# Expansition.net
KiCad netlist of a schematic drawn in Altium Designer
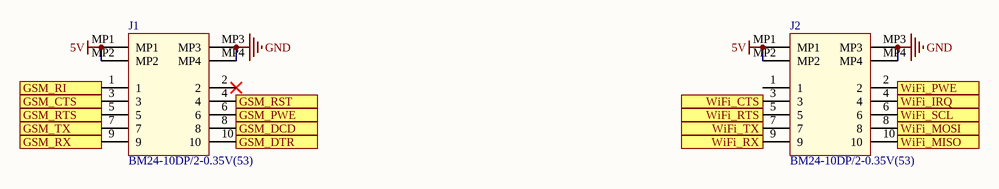
[diagram p0: Expansition.SchDoc]

(export (version "E")
  (design (tool "Eeschema 10.0.6"))
  (components
    (comp (ref "J1")
      (value "BM24-10DP/2-0.35V(53)")
      (footprint "HIROSE BM2410DP")
      (description "Board to Board Connector")
      (fields (field (name "MANUFACTURER") "Hirose"))
      (libsource (lib "yildizIoT Library") (part "12 Pin (10 + 2 Power) B2B Header"))
    )
    (comp (ref "J2")
      (value "BM24-10DP/2-0.35V(53)")
      (footprint "HIROSE BM2410DP")
      (description "Board to Board Connector")
      (fields (field (name "MANUFACTURER") "Hirose"))
      (libsource (lib "yildizIoT Library") (part "12 Pin (10 + 2 Power) B2B Header"))
    )
  )
  (nets
    (net (code "1") (name "/GSM_CTS") (class "Default")
      (node (ref "J1") (pin "3") (pinfunction "3_3") (pintype "passive"))
    )
    (net (code "2") (name "/GSM_DCD") (class "Default")
      (node (ref "J1") (pin "8") (pinfunction "8_8") (pintype "passive"))
    )
    (net (code "3") (name "/GSM_DTR") (class "Default")
      (node (ref "J1") (pin "10") (pinfunction "10_10") (pintype "passive"))
    )
    (net (code "4") (name "/GSM_PWE") (class "Default")
      (node (ref "J1") (pin "6") (pinfunction "6_6") (pintype "passive"))
    )
    (net (code "5") (name "/GSM_RI") (class "Default")
      (node (ref "J1") (pin "1") (pinfunction "1_1") (pintype "passive"))
    )
    (net (code "6") (name "/GSM_RST") (class "Default")
      (node (ref "J1") (pin "4") (pinfunction "4_4") (pintype "passive"))
    )
    (net (code "7") (name "/GSM_RTS") (class "Default")
      (node (ref "J1") (pin "5") (pinfunction "5_5") (pintype "passive"))
    )
    (net (code "8") (name "/GSM_RX") (class "Default")
      (node (ref "J1") (pin "9") (pinfunction "9_9") (pintype "passive"))
    )
    (net (code "9") (name "/GSM_TX") (class "Default")
      (node (ref "J1") (pin "7") (pinfunction "7_7") (pintype "passive"))
    )
    (net (code "10") (name "/WiFi_CTS") (class "Default")
      (node (ref "J2") (pin "3") (pinfunction "3_3") (pintype "passive"))
    )
    (net (code "11") (name "/WiFi_IRQ") (class "Default")
      (node (ref "J2") (pin "4") (pinfunction "4_4") (pintype "passive"))
    )
    (net (code "12") (name "/WiFi_MISO") (class "Default")
      (node (ref "J2") (pin "10") (pinfunction "10_10") (pintype "passive"))
    )
    (net (code "13") (name "/WiFi_MOSI") (class "Default")
      (node (ref "J2") (pin "8") (pinfunction "8_8") (pintype "passive"))
    )
    (net (code "14") (name "/WiFi_PWE") (class "Default")
      (node (ref "J2") (pin "2") (pinfunction "2_2") (pintype "passive"))
    )
    (net (code "15") (name "/WiFi_RTS") (class "Default")
      (node (ref "J2") (pin "5") (pinfunction "5_5") (pintype "passive"))
    )
    (net (code "16") (name "/WiFi_RX") (class "Default")
      (node (ref "J2") (pin "9") (pinfunction "9_9") (pintype "passive"))
    )
    (net (code "17") (name "/WiFi_SCL") (class "Default")
      (node (ref "J2") (pin "6") (pinfunction "6_6") (pintype "passive"))
    )
    (net (code "18") (name "/WiFi_TX") (class "Default")
      (node (ref "J2") (pin "7") (pinfunction "7_7") (pintype "passive"))
    )
    (net (code "19") (name "5V") (class "Default")
      (node (ref "J1") (pin "MP1") (pinfunction "MP1_MP1") (pintype "passive"))
      (node (ref "J1") (pin "MP2") (pinfunction "MP2_MP2") (pintype "passive"))
      (node (ref "J2") (pin "MP1") (pinfunction "MP1_MP1") (pintype "passive"))
      (node (ref "J2") (pin "MP2") (pinfunction "MP2_MP2") (pintype "passive"))
    )
    (net (code "20") (name "GND") (class "Default")
      (node (ref "J1") (pin "MP3") (pinfunction "MP3_MP3") (pintype "passive"))
      (node (ref "J1") (pin "MP4") (pinfunction "MP4_MP4") (pintype "passive"))
      (node (ref "J2") (pin "MP3") (pinfunction "MP3_MP3") (pintype "passive"))
      (node (ref "J2") (pin "MP4") (pinfunction "MP4_MP4") (pintype "passive"))
    )
    (net (code "21") (name "unconnected-(J1-Pad2)") (class "Default")
      (node (ref "J1") (pin "2") (pinfunction "2_2") (pintype "passive+no_connect"))
    )
    (net (code "22") (name "unconnected-(J2-Pad1)") (class "Default")
      (node (ref "J2") (pin "1") (pinfunction "1_1") (pintype "passive"))
    )
  )
)
